# TPA3122_Class-D.net
KiCad netlist of a schematic drawn in EAGLE
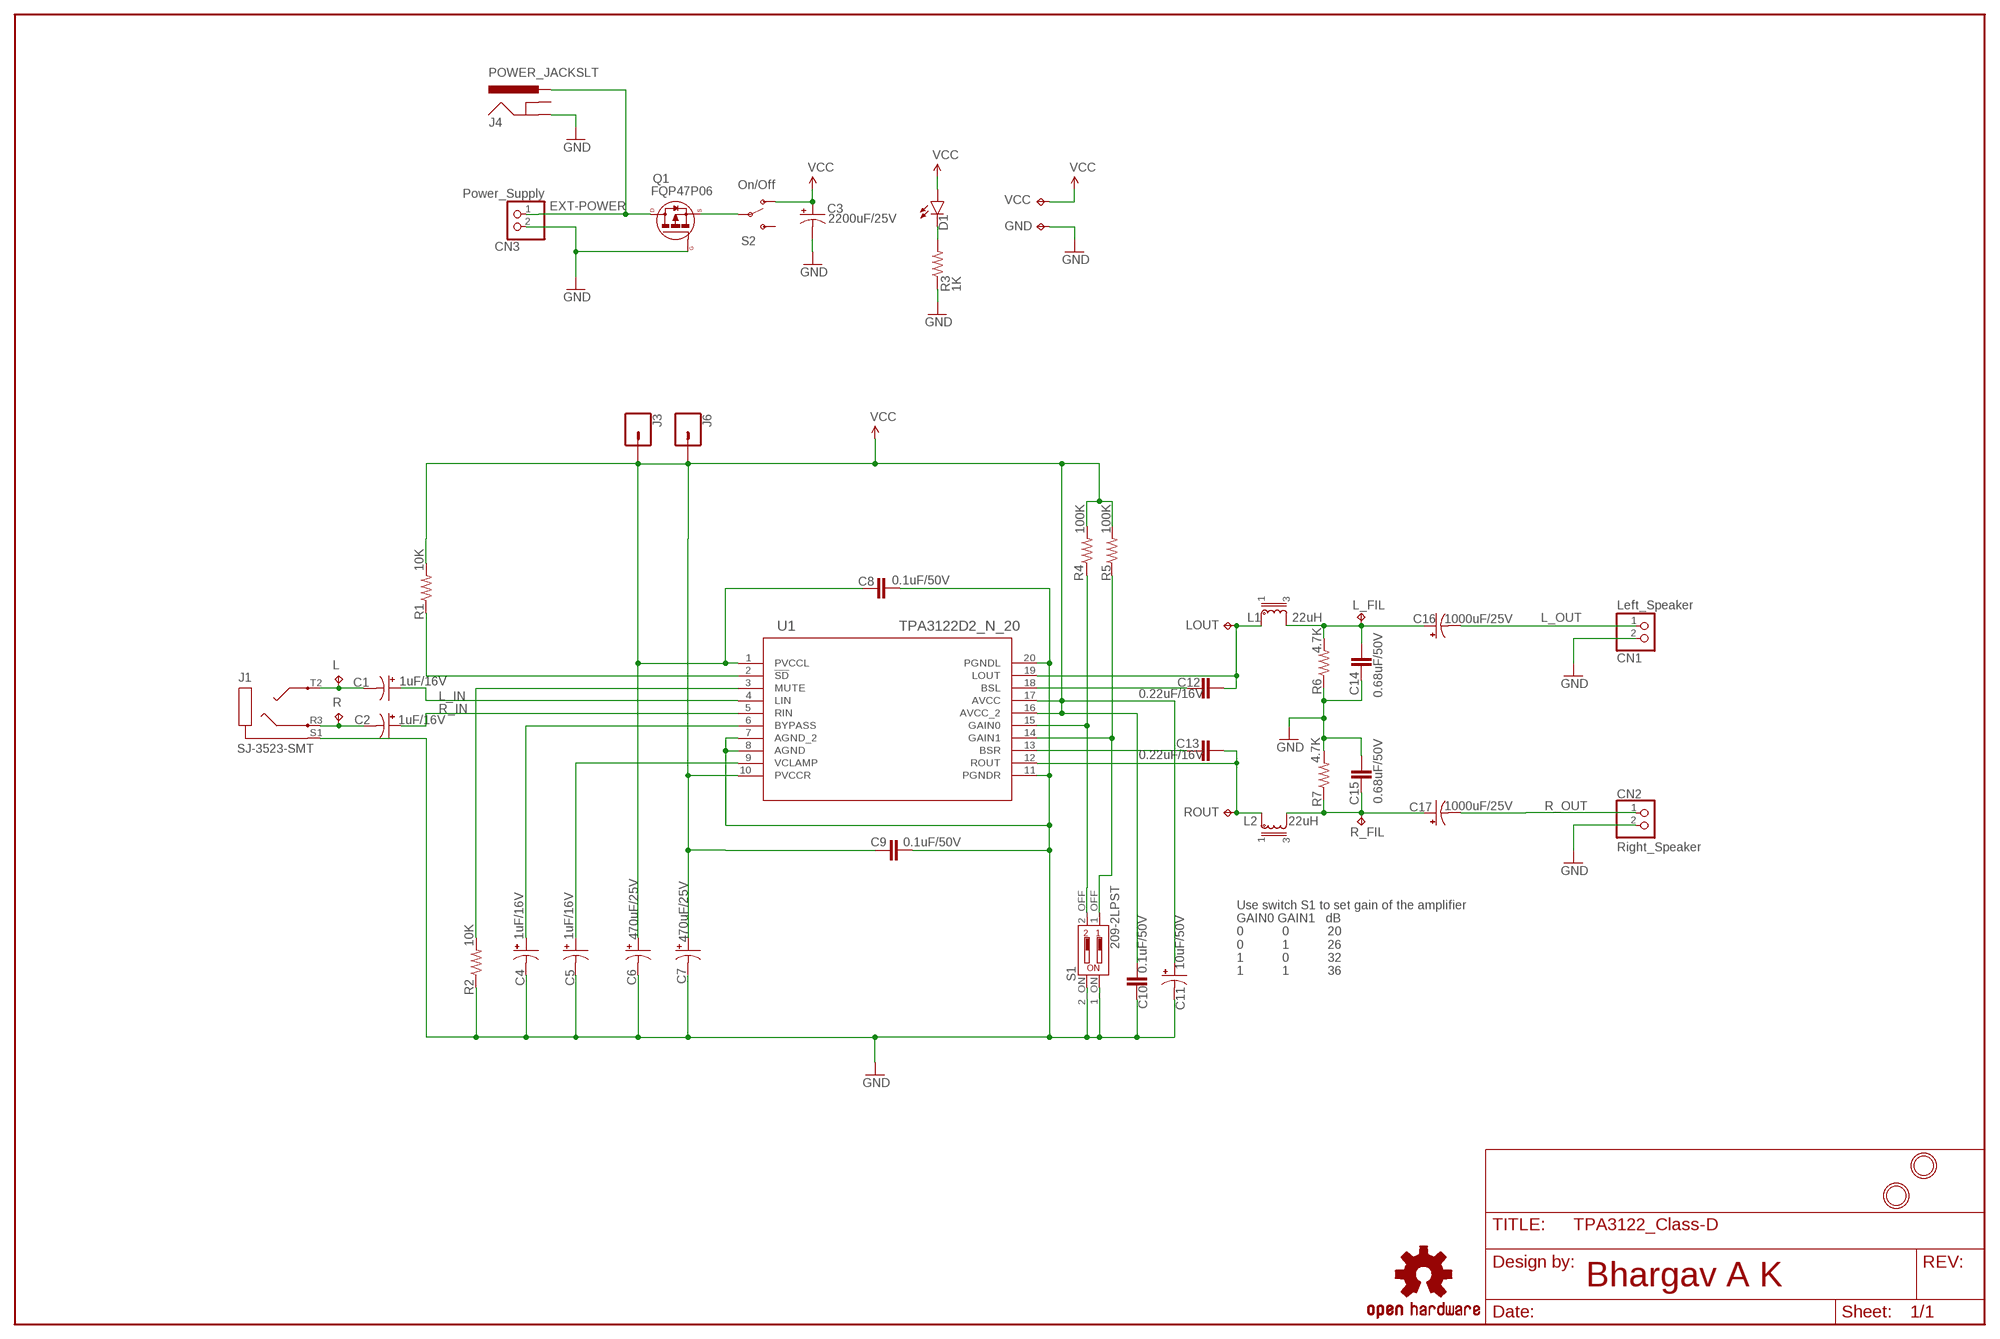
[diagram p0: schematic, sheet 1]

(export (version "E")
  (design (tool "Eeschema 10.0.6"))
  (components
    (comp (ref "C1")
      (value "1uF/16V")
      (footprint "eagle-import:E2,5-5")
      (libsource (lib "eagle-import") (part "CPOL-USE2.5-5"))
    )
    (comp (ref "C2")
      (value "1uF/16V")
      (footprint "eagle-import:E2,5-5")
      (libsource (lib "eagle-import") (part "CPOL-USE2.5-5"))
    )
    (comp (ref "C3")
      (value "2200uF/25V")
      (footprint "eagle-import:E5-13")
      (libsource (lib "eagle-import") (part "CPOL-USE5-13"))
    )
    (comp (ref "C4")
      (value "1uF/16V")
      (footprint "eagle-import:E2,5-5")
      (libsource (lib "eagle-import") (part "CPOL-USE2.5-5"))
    )
    (comp (ref "C5")
      (value "1uF/16V")
      (footprint "eagle-import:E2,5-5")
      (libsource (lib "eagle-import") (part "CPOL-USE2.5-5"))
    )
    (comp (ref "C6")
      (value "470uF/25V")
      (footprint "eagle-import:E5-10,5")
      (libsource (lib "eagle-import") (part "CPOL-USE5-10.5"))
    )
    (comp (ref "C7")
      (value "470uF/25V")
      (footprint "eagle-import:E5-10,5")
      (libsource (lib "eagle-import") (part "CPOL-USE5-10.5"))
    )
    (comp (ref "C8")
      (value "0.1uF/50V")
      (footprint "eagle-import:C050-024X044")
      (libsource (lib "eagle-import") (part "C-EU050-024X044"))
    )
    (comp (ref "C9")
      (value "0.1uF/50V")
      (footprint "eagle-import:C050-024X044")
      (libsource (lib "eagle-import") (part "C-EU050-024X044"))
    )
    (comp (ref "C10")
      (value "0.1uF/50V")
      (footprint "eagle-import:C050-024X044")
      (libsource (lib "eagle-import") (part "C-EU050-024X044"))
    )
    (comp (ref "C11")
      (value "10uF/50V")
      (footprint "eagle-import:E2,5-5")
      (libsource (lib "eagle-import") (part "CPOL-USE2.5-5"))
    )
    (comp (ref "C12")
      (value "0.22uF/16V")
      (footprint "eagle-import:C050-024X044")
      (libsource (lib "eagle-import") (part "C-EU050-024X044"))
    )
    (comp (ref "C13")
      (value "0.22uF/16V")
      (footprint "eagle-import:C050-024X044")
      (libsource (lib "eagle-import") (part "C-EU050-024X044"))
    )
    (comp (ref "C14")
      (value "0.68uF/50V")
      (footprint "eagle-import:C050-024X044")
      (libsource (lib "eagle-import") (part "C-EU050-024X044"))
    )
    (comp (ref "C15")
      (value "0.68uF/50V")
      (footprint "eagle-import:C050-024X044")
      (libsource (lib "eagle-import") (part "C-EU050-024X044"))
    )
    (comp (ref "C16")
      (value "1000uF/25V")
      (footprint "eagle-import:E5-10,5")
      (libsource (lib "eagle-import") (part "CPOL-USE5-10.5"))
    )
    (comp (ref "C17")
      (value "1000uF/25V")
      (footprint "eagle-import:E5-10,5")
      (libsource (lib "eagle-import") (part "CPOL-USE5-10.5"))
    )
    (comp (ref "CN1")
      (value "Left_Speaker")
      (footprint "eagle-import:JST-PH-2-THM")
      (libsource (lib "eagle-import") (part "JST_2PIN-THM"))
    )
    (comp (ref "CN2")
      (value "Right_Speaker")
      (footprint "eagle-import:JST-PH-2-THM")
      (libsource (lib "eagle-import") (part "JST_2PIN-THM"))
    )
    (comp (ref "CN3")
      (value "Power_Supply")
      (footprint "eagle-import:JST-PH-2-THM")
      (libsource (lib "eagle-import") (part "JST_2PIN-THM"))
    )
    (comp (ref "D1")
      (value "LED3MM")
      (footprint "eagle-import:LED_3MM")
      (libsource (lib "eagle-import") (part "LED3MM"))
    )
    (comp (ref "GND")
      (value "TPB2,54")
      (footprint "eagle-import:B2,54")
      (libsource (lib "eagle-import") (part "TPB2,54"))
    )
    (comp (ref "J1")
      (value "SJ-3523-SMT")
      (footprint "eagle-import:SJ-3523-SMT")
      (fields (field (name "MANUFACTURER") "CUI Inc"))
      (libsource (lib "eagle-import") (part "SJ-3523-SMT"))
    )
    (comp (ref "J3")
      (value "CONN_01")
      (footprint "eagle-import:1X01")
      (libsource (lib "eagle-import") (part "CONN_01"))
    )
    (comp (ref "J4")
      (value "POWER_JACKSLT")
      (footprint "eagle-import:POWER_JACK_SLOT")
      (libsource (lib "eagle-import") (part "POWER_JACKSLT"))
    )
    (comp (ref "J6")
      (value "CONN_01")
      (footprint "eagle-import:1X01")
      (libsource (lib "eagle-import") (part "CONN_01"))
    )
    (comp (ref "L")
      (value "TPB2,54")
      (footprint "eagle-import:B2,54")
      (libsource (lib "eagle-import") (part "TPB2,54"))
    )
    (comp (ref "L1")
      (value "22uH")
      (footprint "eagle-import:MURATA_1200RS")
      (libsource (lib "eagle-import") (part "MURATA_1200RS"))
    )
    (comp (ref "L2")
      (value "22uH")
      (footprint "eagle-import:MURATA_1200RS")
      (libsource (lib "eagle-import") (part "MURATA_1200RS"))
    )
    (comp (ref "LOGO1")
      (value "OSHW-LOGOM")
      (footprint "eagle-import:OSHW-LOGO-M")
      (libsource (lib "eagle-import") (part "OSHW-LOGOM"))
    )
    (comp (ref "LOUT")
      (value "TPB2,54")
      (footprint "eagle-import:B2,54")
      (libsource (lib "eagle-import") (part "TPB2,54"))
    )
    (comp (ref "L_FIL")
      (value "TPB2,54")
      (footprint "eagle-import:B2,54")
      (libsource (lib "eagle-import") (part "TPB2,54"))
    )
    (comp (ref "Q1")
      (value "FQP47P06")
      (footprint "eagle-import:TO220")
      (libsource (lib "eagle-import") (part "FQP47P06"))
    )
    (comp (ref "R")
      (value "TPB2,54")
      (footprint "eagle-import:B2,54")
      (libsource (lib "eagle-import") (part "TPB2,54"))
    )
    (comp (ref "R1")
      (value "10K")
      (footprint "eagle-import:0309_10")
      (libsource (lib "eagle-import") (part "R-US_0309/10"))
    )
    (comp (ref "R2")
      (value "10K")
      (footprint "eagle-import:0309_10")
      (libsource (lib "eagle-import") (part "R-US_0309/10"))
    )
    (comp (ref "R3")
      (value "1K")
      (footprint "eagle-import:0309_10")
      (libsource (lib "eagle-import") (part "R-US_0309/10"))
    )
    (comp (ref "R4")
      (value "100K")
      (footprint "eagle-import:0309_10")
      (libsource (lib "eagle-import") (part "R-US_0309/10"))
    )
    (comp (ref "R5")
      (value "100K")
      (footprint "eagle-import:0309_10")
      (libsource (lib "eagle-import") (part "R-US_0309/10"))
    )
    (comp (ref "R6")
      (value "4.7K")
      (footprint "eagle-import:0309_10")
      (libsource (lib "eagle-import") (part "R-US_0309/10"))
    )
    (comp (ref "R7")
      (value "4.7K")
      (footprint "eagle-import:0309_10")
      (libsource (lib "eagle-import") (part "R-US_0309/10"))
    )
    (comp (ref "ROUT")
      (value "TPB2,54")
      (footprint "eagle-import:B2,54")
      (libsource (lib "eagle-import") (part "TPB2,54"))
    )
    (comp (ref "R_FIL")
      (value "TPB2,54")
      (footprint "eagle-import:B2,54")
      (libsource (lib "eagle-import") (part "TPB2,54"))
    )
    (comp (ref "S1")
      (value "209-2LPST")
      (footprint "eagle-import:209-2LPST")
      (libsource (lib "eagle-import") (part "209-2LPST"))
    )
    (comp (ref "S2")
      (value "SWITCH-SPDTPTH")
      (footprint "eagle-import:SWITCH-SPDT")
      (libsource (lib "eagle-import") (part "SWITCH-SPDTPTH"))
    )
    (comp (ref "U$2")
      (value "MOUNTINGHOLE2.5_THICK")
      (footprint "eagle-import:MOUNTINGHOLE_2.5_PLATED_THICK")
      (libsource (lib "eagle-import") (part "MOUNTINGHOLE2.5_THICK"))
    )
    (comp (ref "U$3")
      (value "MOUNTINGHOLE2.5_THICK")
      (footprint "eagle-import:MOUNTINGHOLE_2.5_PLATED_THICK")
      (libsource (lib "eagle-import") (part "MOUNTINGHOLE2.5_THICK"))
    )
    (comp (ref "U1")
      (value "TPA3122D2_N_20")
      (footprint "eagle-import:N20")
      (libsource (lib "eagle-import") (part "TPA3122D2_N_20"))
    )
    (comp (ref "VCC")
      (value "TPB2,54")
      (footprint "eagle-import:B2,54")
      (libsource (lib "eagle-import") (part "TPB2,54"))
    )
  )
  (nets
    (net (code "1") (name "/EXT-POWER") (class "Default")
      (node (ref "CN3") (pin "1") (pinfunction "1_VCC_1") (pintype "passive"))
      (node (ref "J4") (pin "PWR") (pinfunction "PWR_PWR") (pintype "bidirectional"))
      (node (ref "Q1") (pin "D") (pinfunction "D_D") (pintype "passive"))
    )
    (net (code "2") (name "/L_IN") (class "Default")
      (node (ref "C1") (pin "+") (pinfunction "+_+") (pintype "passive"))
      (node (ref "U1") (pin "4") (pinfunction "LIN_4") (pintype "input"))
    )
    (net (code "3") (name "/L_OUT") (class "Default")
      (node (ref "C16") (pin "-") (pinfunction "-_-") (pintype "passive"))
      (node (ref "CN1") (pin "1") (pinfunction "1_VCC_1") (pintype "passive"))
    )
    (net (code "4") (name "/R_IN") (class "Default")
      (node (ref "C2") (pin "+") (pinfunction "+_+") (pintype "passive"))
      (node (ref "U1") (pin "5") (pinfunction "RIN_5") (pintype "input"))
    )
    (net (code "5") (name "/R_OUT") (class "Default")
      (node (ref "C17") (pin "-") (pinfunction "-_-") (pintype "passive"))
      (node (ref "CN2") (pin "1") (pinfunction "1_VCC_1") (pintype "passive"))
    )
    (net (code "6") (name "GND") (class "Default")
      (node (ref "C10") (pin "2") (pinfunction "2_2") (pintype "passive"))
      (node (ref "C11") (pin "-") (pinfunction "-_-") (pintype "passive"))
      (node (ref "C14") (pin "2") (pinfunction "2_2") (pintype "passive"))
      (node (ref "C15") (pin "1") (pinfunction "1_1") (pintype "passive"))
      (node (ref "C3") (pin "-") (pinfunction "-_-") (pintype "passive"))
      (node (ref "C4") (pin "-") (pinfunction "-_-") (pintype "passive"))
      (node (ref "C5") (pin "-") (pinfunction "-_-") (pintype "passive"))
      (node (ref "C6") (pin "-") (pinfunction "-_-") (pintype "passive"))
      (node (ref "C7") (pin "-") (pinfunction "-_-") (pintype "passive"))
      (node (ref "C8") (pin "2") (pinfunction "2_2") (pintype "passive"))
      (node (ref "C9") (pin "2") (pinfunction "2_2") (pintype "passive"))
      (node (ref "CN1") (pin "2") (pinfunction "2_GND_2") (pintype "passive"))
      (node (ref "CN2") (pin "2") (pinfunction "2_GND_2") (pintype "passive"))
      (node (ref "CN3") (pin "2") (pinfunction "2_GND_2") (pintype "passive"))
      (node (ref "GND") (pin "TP") (pinfunction "TP_TP") (pintype "input"))
      (node (ref "J1") (pin "S1") (pinfunction "S1_S1") (pintype "passive"))
      (node (ref "J4") (pin "GND@2") (pinfunction "GND_GND@2") (pintype "bidirectional"))
      (node (ref "Q1") (pin "G") (pinfunction "G_G") (pintype "passive"))
      (node (ref "R2") (pin "1") (pinfunction "1_1") (pintype "passive"))
      (node (ref "R3") (pin "1") (pinfunction "1_1") (pintype "passive"))
      (node (ref "R6") (pin "1") (pinfunction "1_1") (pintype "passive"))
      (node (ref "R7") (pin "2") (pinfunction "2_2") (pintype "passive"))
      (node (ref "S1") (pin "1_ON") (pinfunction "1_ON_1_ON") (pintype "bidirectional"))
      (node (ref "S1") (pin "2_ON") (pinfunction "2_ON_2_ON") (pintype "bidirectional"))
      (node (ref "U1") (pin "11") (pinfunction "PGNDR_11") (pintype "power_in"))
      (node (ref "U1") (pin "20") (pinfunction "PGNDL_20") (pintype "power_in"))
      (node (ref "U1") (pin "7") (pinfunction "AGND_2_7") (pintype "power_in"))
      (node (ref "U1") (pin "8") (pinfunction "AGND_8") (pintype "power_in"))
    )
    (net (code "7") (name "Net-(C1-Pad-)") (class "Default")
      (node (ref "C1") (pin "-") (pinfunction "-_-") (pintype "passive"))
      (node (ref "J1") (pin "T2") (pinfunction "T2_T2") (pintype "passive"))
      (node (ref "L") (pin "TP") (pinfunction "TP_TP") (pintype "input"))
    )
    (net (code "8") (name "Net-(C2-Pad-)") (class "Default")
      (node (ref "C2") (pin "-") (pinfunction "-_-") (pintype "passive"))
      (node (ref "J1") (pin "R3") (pinfunction "R3_R3") (pintype "passive"))
      (node (ref "R") (pin "TP") (pinfunction "TP_TP") (pintype "input"))
    )
    (net (code "9") (name "Net-(C14-Pad1)") (class "Default")
      (node (ref "C14") (pin "1") (pinfunction "1_1") (pintype "passive"))
      (node (ref "C16") (pin "+") (pinfunction "+_+") (pintype "passive"))
      (node (ref "L1") (pin "3") (pinfunction "3_3") (pintype "passive"))
      (node (ref "L_FIL") (pin "TP") (pinfunction "TP_TP") (pintype "input"))
      (node (ref "R6") (pin "2") (pinfunction "2_2") (pintype "passive"))
    )
    (net (code "10") (name "Net-(C15-Pad2)") (class "Default")
      (node (ref "C15") (pin "2") (pinfunction "2_2") (pintype "passive"))
      (node (ref "C17") (pin "+") (pinfunction "+_+") (pintype "passive"))
      (node (ref "L2") (pin "3") (pinfunction "3_3") (pintype "passive"))
      (node (ref "R7") (pin "1") (pinfunction "1_1") (pintype "passive"))
      (node (ref "R_FIL") (pin "TP") (pinfunction "TP_TP") (pintype "input"))
    )
    (net (code "11") (name "Net-(D1-C)") (class "Default")
      (node (ref "D1") (pin "K") (pinfunction "C_K") (pintype "passive"))
      (node (ref "R3") (pin "2") (pinfunction "2_2") (pintype "passive"))
    )
    (net (code "12") (name "Net-(S2-P)") (class "Default")
      (node (ref "Q1") (pin "S") (pinfunction "S_S") (pintype "passive"))
      (node (ref "S2") (pin "2") (pinfunction "P_2") (pintype "passive"))
    )
    (net (code "13") (name "Net-(U1-BSL)") (class "Default")
      (node (ref "C12") (pin "1") (pinfunction "1_1") (pintype "passive"))
      (node (ref "U1") (pin "18") (pinfunction "BSL_18") (pintype "bidirectional"))
    )
    (net (code "14") (name "Net-(U1-BSR)") (class "Default")
      (node (ref "C13") (pin "1") (pinfunction "1_1") (pintype "passive"))
      (node (ref "U1") (pin "13") (pinfunction "BSR_13") (pintype "bidirectional"))
    )
    (net (code "15") (name "Net-(U1-BYPASS)") (class "Default")
      (node (ref "C4") (pin "+") (pinfunction "+_+") (pintype "passive"))
      (node (ref "U1") (pin "6") (pinfunction "BYPASS_6") (pintype "output"))
    )
    (net (code "16") (name "Net-(U1-GAIN0)") (class "Default")
      (node (ref "R4") (pin "1") (pinfunction "1_1") (pintype "passive"))
      (node (ref "S1") (pin "2_OFF") (pinfunction "2_OFF_2_OFF") (pintype "bidirectional"))
      (node (ref "U1") (pin "15") (pinfunction "GAIN0_15") (pintype "input"))
    )
    (net (code "17") (name "Net-(U1-GAIN1)") (class "Default")
      (node (ref "R5") (pin "1") (pinfunction "1_1") (pintype "passive"))
      (node (ref "S1") (pin "1_OFF") (pinfunction "1_OFF_1_OFF") (pintype "bidirectional"))
      (node (ref "U1") (pin "14") (pinfunction "GAIN1_14") (pintype "input"))
    )
    (net (code "18") (name "Net-(U1-LOUT)") (class "Default")
      (node (ref "C12") (pin "2") (pinfunction "2_2") (pintype "passive"))
      (node (ref "L1") (pin "1") (pinfunction "1_1") (pintype "passive"))
      (node (ref "LOUT") (pin "TP") (pinfunction "TP_TP") (pintype "input"))
      (node (ref "U1") (pin "19") (pinfunction "LOUT_19") (pintype "output"))
    )
    (net (code "19") (name "Net-(U1-MUTE)") (class "Default")
      (node (ref "R2") (pin "2") (pinfunction "2_2") (pintype "passive"))
      (node (ref "U1") (pin "3") (pinfunction "MUTE_3") (pintype "input"))
    )
    (net (code "20") (name "Net-(U1-ROUT)") (class "Default")
      (node (ref "C13") (pin "2") (pinfunction "2_2") (pintype "passive"))
      (node (ref "L2") (pin "1") (pinfunction "1_1") (pintype "passive"))
      (node (ref "ROUT") (pin "TP") (pinfunction "TP_TP") (pintype "input"))
      (node (ref "U1") (pin "12") (pinfunction "ROUT_12") (pintype "output"))
    )
    (net (code "21") (name "Net-(U1-VCLAMP)") (class "Default")
      (node (ref "C5") (pin "+") (pinfunction "+_+") (pintype "passive"))
      (node (ref "U1") (pin "9") (pinfunction "VCLAMP_9") (pintype "power_in"))
    )
    (net (code "22") (name "Net-(U1-~{SD})") (class "Default")
      (node (ref "R1") (pin "1") (pinfunction "1_1") (pintype "passive"))
      (node (ref "U1") (pin "2") (pinfunction "~{SD}_2") (pintype "input"))
    )
    (net (code "23") (name "VCC") (class "Default")
      (node (ref "C10") (pin "1") (pinfunction "1_1") (pintype "passive"))
      (node (ref "C11") (pin "+") (pinfunction "+_+") (pintype "passive"))
      (node (ref "C3") (pin "+") (pinfunction "+_+") (pintype "passive"))
      (node (ref "C6") (pin "+") (pinfunction "+_+") (pintype "passive"))
      (node (ref "C7") (pin "+") (pinfunction "+_+") (pintype "passive"))
      (node (ref "C8") (pin "1") (pinfunction "1_1") (pintype "passive"))
      (node (ref "C9") (pin "1") (pinfunction "1_1") (pintype "passive"))
      (node (ref "D1") (pin "A") (pinfunction "A_A") (pintype "passive"))
      (node (ref "J3") (pin "1") (pinfunction "1_1") (pintype "passive"))
      (node (ref "J6") (pin "1") (pinfunction "1_1") (pintype "passive"))
      (node (ref "R1") (pin "2") (pinfunction "2_2") (pintype "passive"))
      (node (ref "R4") (pin "2") (pinfunction "2_2") (pintype "passive"))
      (node (ref "R5") (pin "2") (pinfunction "2_2") (pintype "passive"))
      (node (ref "S2") (pin "1") (pinfunction "O_1") (pintype "passive"))
      (node (ref "U1") (pin "1") (pinfunction "PVCCL_1") (pintype "power_in"))
      (node (ref "U1") (pin "10") (pinfunction "PVCCR_10") (pintype "power_in"))
      (node (ref "U1") (pin "16") (pinfunction "AVCC_2_16") (pintype "power_in"))
      (node (ref "U1") (pin "17") (pinfunction "AVCC_17") (pintype "power_in"))
      (node (ref "VCC") (pin "TP") (pinfunction "TP_TP") (pintype "input"))
    )
    (net (code "24") (name "unconnected-(J4-GNDBREAK-PadGND@1)") (class "Default")
      (node (ref "J4") (pin "GND@1") (pinfunction "GNDBREAK_GND@1") (pintype "bidirectional"))
    )
    (net (code "25") (name "unconnected-(S2-S-Pad3)") (class "Default")
      (node (ref "S2") (pin "3") (pinfunction "S_3") (pintype "passive"))
    )
  )
)
